# EmonDCShieldv0_1.net
KiCad netlist of a schematic drawn in EAGLE
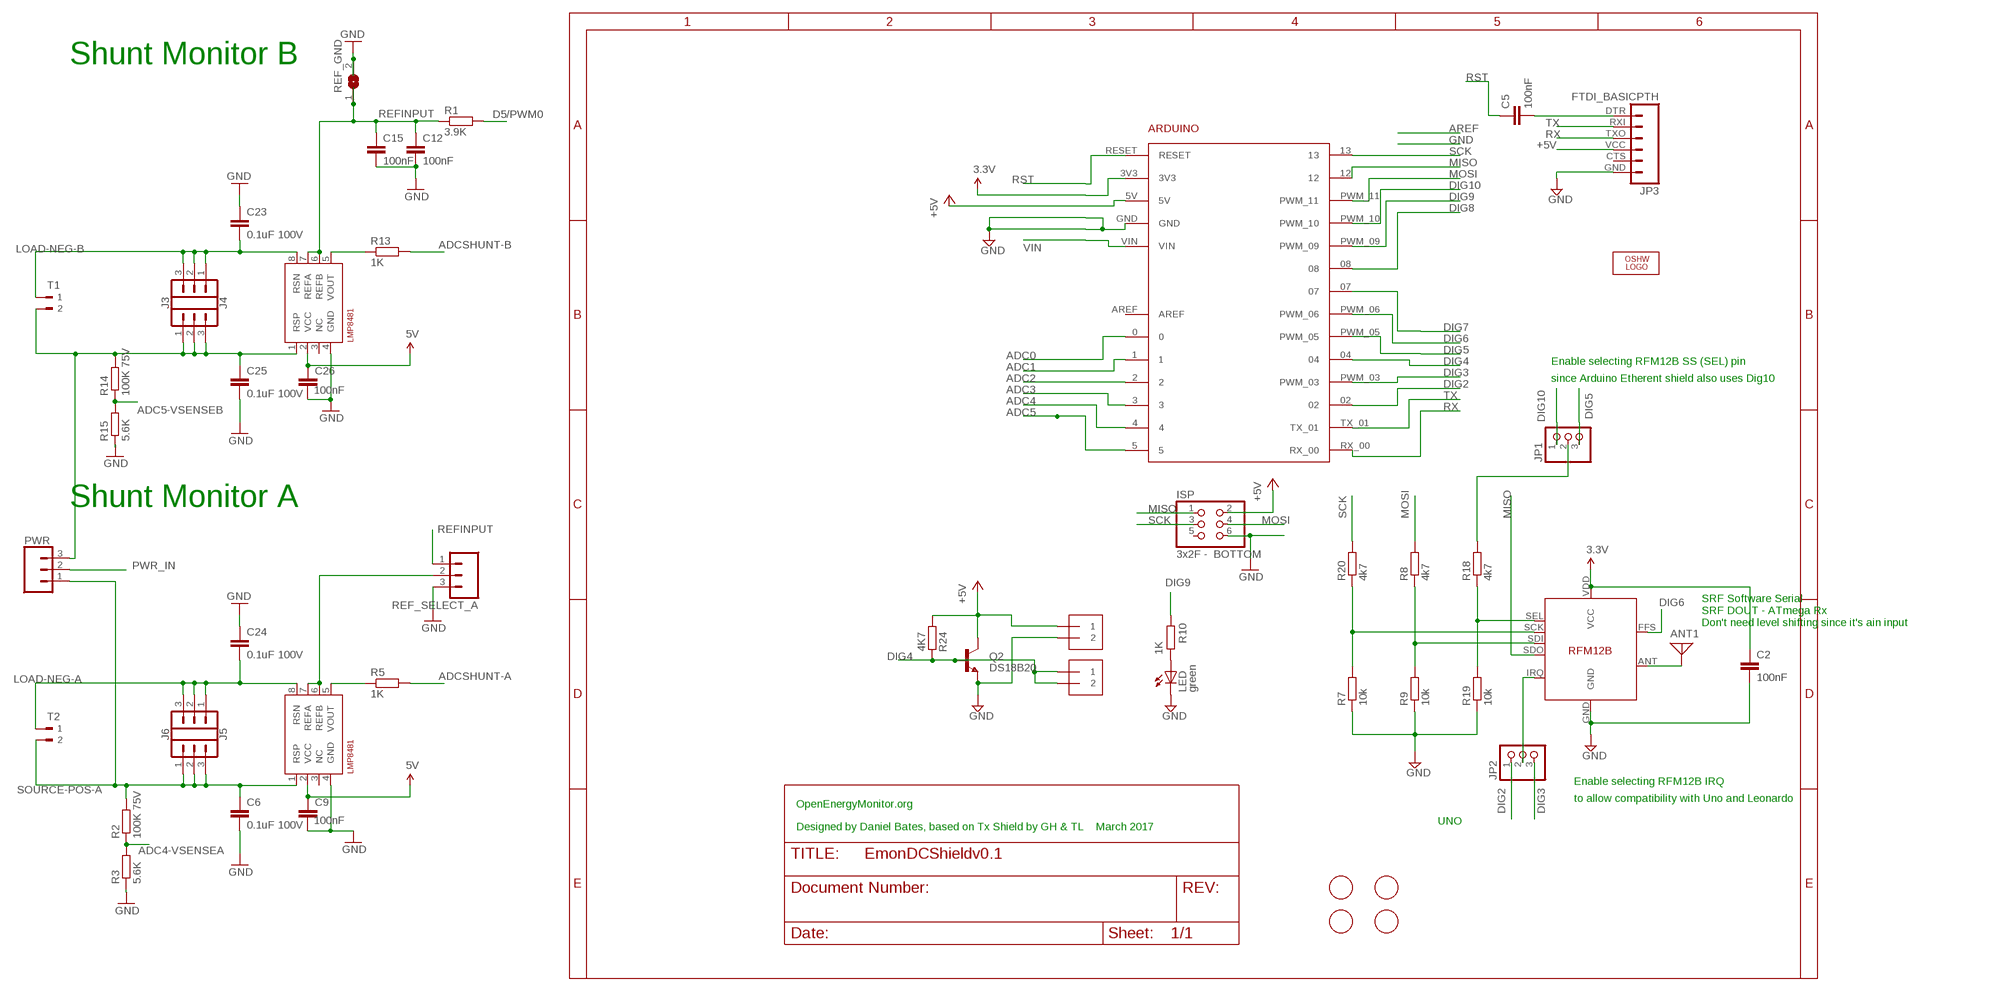
[diagram p0: schematic, sheet 1]

(export (version "E")
  (design (tool "Eeschema 10.0.6"))
  (components
    (comp (ref "ANT1")
      (value "ANTENNA")
      (footprint "eagle-import:PAD-01")
      (libsource (lib "eagle-import") (part "ANTENNA"))
    )
    (comp (ref "ARDUINO1")
      (value "ARDUINO2")
      (footprint "eagle-import:ARDUINO2")
      (libsource (lib "eagle-import") (part "ARDUINO2"))
    )
    (comp (ref "C2")
      (value "100nF")
      (footprint "eagle-import:C0603")
      (libsource (lib "eagle-import") (part "C-EUC0603"))
    )
    (comp (ref "C5")
      (value "100nF")
      (footprint "eagle-import:C0603")
      (libsource (lib "eagle-import") (part "C-EUC0603"))
    )
    (comp (ref "C6")
      (value "0.1uF 100V")
      (footprint "eagle-import:C0603")
      (fields (field (name "MPN") "C1608X7S2A104K080AB"))
      (libsource (lib "eagle-import") (part "C-EUC0603"))
    )
    (comp (ref "C9")
      (value "100nF")
      (footprint "eagle-import:C0603")
      (fields (field (name "MPN") "C1608X7S2A104K080AB"))
      (libsource (lib "eagle-import") (part "C-EUC0603"))
    )
    (comp (ref "C12")
      (value "100nF")
      (footprint "eagle-import:C0603")
      (libsource (lib "eagle-import") (part "C-EUC0603"))
    )
    (comp (ref "C15")
      (value "100nF")
      (footprint "eagle-import:C0603")
      (fields (field (name "MPN") "C1608X7S2A104K080AB"))
      (libsource (lib "eagle-import") (part "C-EUC0603"))
    )
    (comp (ref "C23")
      (value "0.1uF 100V")
      (footprint "eagle-import:C0603")
      (fields (field (name "MPN") "C1608X7S2A104K080AB"))
      (libsource (lib "eagle-import") (part "C-EUC0603"))
    )
    (comp (ref "C24")
      (value "0.1uF 100V")
      (footprint "eagle-import:C0603")
      (fields (field (name "MPN") "C1608X7S2A104K080AB"))
      (libsource (lib "eagle-import") (part "C-EUC0603"))
    )
    (comp (ref "C25")
      (value "0.1uF 100V")
      (footprint "eagle-import:C0603")
      (fields (field (name "MPN") "C1608X7S2A104K080AB"))
      (libsource (lib "eagle-import") (part "C-EUC0603"))
    )
    (comp (ref "C26")
      (value "100nF")
      (footprint "eagle-import:C0603")
      (fields (field (name "MPN") "C1608X7S2A104K080AB"))
      (libsource (lib "eagle-import") (part "C-EUC0603"))
    )
    (comp (ref "ISP")
      (value "3x2F - BOTTOM")
      (footprint "eagle-import:2X03")
      (libsource (lib "eagle-import") (part "PINHD-2X3"))
    )
    (comp (ref "J1")
      (value "1X2-3.5MM")
      (footprint "eagle-import:1X2-3.5MM")
      (libsource (lib "eagle-import") (part "1X2-3.5MM"))
    )
    (comp (ref "J2")
      (value "1X2-3.5MM")
      (footprint "eagle-import:1X2-3.5MM")
      (libsource (lib "eagle-import") (part "1X2-3.5MM"))
    )
    (comp (ref "J3")
      (value "CONN_03")
      (footprint "eagle-import:1X03")
      (libsource (lib "eagle-import") (part "CONN_03"))
    )
    (comp (ref "J4")
      (value "CONN_03")
      (footprint "eagle-import:1X03")
      (libsource (lib "eagle-import") (part "CONN_03"))
    )
    (comp (ref "J5")
      (value "CONN_03")
      (footprint "eagle-import:1X03")
      (libsource (lib "eagle-import") (part "CONN_03"))
    )
    (comp (ref "J6")
      (value "CONN_03")
      (footprint "eagle-import:1X03")
      (libsource (lib "eagle-import") (part "CONN_03"))
    )
    (comp (ref "JP1")
      (value "PINHD-1X3")
      (footprint "eagle-import:1X03")
      (libsource (lib "eagle-import") (part "PINHD-1X3"))
    )
    (comp (ref "JP2")
      (value "PINHD-1X3")
      (footprint "eagle-import:1X03")
      (libsource (lib "eagle-import") (part "PINHD-1X3"))
    )
    (comp (ref "JP3")
      (value "FTDI_BASICPTH")
      (footprint "eagle-import:FTDI_BASIC")
      (libsource (lib "eagle-import") (part "FTDI_BASICPTH"))
    )
    (comp (ref "LED")
      (value "green")
      (footprint "eagle-import:CHIPLED_0805")
      (libsource (lib "eagle-import") (part "LEDCHIPLED_0805"))
    )
    (comp (ref "LOGO1")
      (value "OSHW_LOGO_10MILX0200-NT")
      (footprint "eagle-import:OSHW_10X200_NOTEXT")
      (libsource (lib "eagle-import") (part "OSHW_LOGO_10MILX0200-NT"))
    )
    (comp (ref "PWR")
      (value "CONN_03")
      (footprint "eagle-import:1X03")
      (libsource (lib "eagle-import") (part "CONN_03"))
    )
    (comp (ref "Q2")
      (value "DS18B20")
      (footprint "eagle-import:TO-92")
      (libsource (lib "eagle-import") (part "TRANSISTOR_NPNTO92"))
    )
    (comp (ref "R1")
      (value "3.9K")
      (footprint "eagle-import:R0603")
      (libsource (lib "eagle-import") (part "R-EU_R0603"))
    )
    (comp (ref "R2")
      (value "100K 75V")
      (footprint "eagle-import:R0603")
      (fields (field (name "MPN") "MCWR06X1003FTL"))
      (libsource (lib "eagle-import") (part "R-EU_R0603"))
    )
    (comp (ref "R3")
      (value "5.6K")
      (footprint "eagle-import:R0603")
      (fields (field (name "MPN") " MCWR06X5901FTL"))
      (libsource (lib "eagle-import") (part "R-EU_R0603"))
    )
    (comp (ref "R5")
      (value "1K")
      (footprint "eagle-import:R0603")
      (libsource (lib "eagle-import") (part "R-EU_R0603"))
    )
    (comp (ref "R7")
      (value "10k")
      (footprint "eagle-import:R0603")
      (libsource (lib "eagle-import") (part "R-EU_R0603"))
    )
    (comp (ref "R8")
      (value "4k7")
      (footprint "eagle-import:R0603")
      (libsource (lib "eagle-import") (part "R-EU_R0603"))
    )
    (comp (ref "R9")
      (value "10k")
      (footprint "eagle-import:R0603")
      (libsource (lib "eagle-import") (part "R-EU_R0603"))
    )
    (comp (ref "R10")
      (value "1K")
      (footprint "eagle-import:R0603")
      (libsource (lib "eagle-import") (part "R-EU_R0603"))
    )
    (comp (ref "R13")
      (value "1K")
      (footprint "eagle-import:R0603")
      (libsource (lib "eagle-import") (part "R-EU_R0603"))
    )
    (comp (ref "R14")
      (value "100K 75V")
      (footprint "eagle-import:R0603")
      (fields (field (name "MPN") "MCWR06X1003FTL"))
      (libsource (lib "eagle-import") (part "R-EU_R0603"))
    )
    (comp (ref "R15")
      (value "5.6K")
      (footprint "eagle-import:R0603")
      (fields (field (name "MPN") " MCWR06X5901FTL"))
      (libsource (lib "eagle-import") (part "R-EU_R0603"))
    )
    (comp (ref "R18")
      (value "4k7")
      (footprint "eagle-import:R0603")
      (libsource (lib "eagle-import") (part "R-EU_R0603"))
    )
    (comp (ref "R19")
      (value "10k")
      (footprint "eagle-import:R0603")
      (libsource (lib "eagle-import") (part "R-EU_R0603"))
    )
    (comp (ref "R20")
      (value "4k7")
      (footprint "eagle-import:R0603")
      (libsource (lib "eagle-import") (part "R-EU_R0603"))
    )
    (comp (ref "R24")
      (value "4K7")
      (footprint "eagle-import:R0603")
      (libsource (lib "eagle-import") (part "R-EU_R0603"))
    )
    (comp (ref "REF_GND")
      (value "SJ")
      (footprint "eagle-import:SJ")
      (libsource (lib "eagle-import") (part "SJ"))
    )
    (comp (ref "REF_SELECT_A")
      (value "2212S-02SG-85")
      (footprint "eagle-import:1X03")
      (fields (field (name "MF") "MULTICOMP"))
      (libsource (lib "eagle-import") (part "CONN_03"))
    )
    (comp (ref "SHUNTMON-A")
      (value "LMP8481")
      (footprint "eagle-import:S-PDSO-G08")
      (fields (field (name "MF") "TEXAS INSTRUMENTS") (field (name "MPN") "LMP8481MME-S/NOPB"))
      (libsource (lib "eagle-import") (part "LMP8481LMP8481-H"))
    )
    (comp (ref "SHUNTMON-B")
      (value "LMP8481")
      (footprint "eagle-import:S-PDSO-G08")
      (fields (field (name "MF") "TEXAS INSTRUMENTS") (field (name "MPN") "LMP8481MME-H/NOPB"))
      (libsource (lib "eagle-import") (part "LMP8481LMP8481-H"))
    )
    (comp (ref "T1")
      (value "180-2")
      (footprint "eagle-import:180-2")
      (libsource (lib "eagle-import") (part "180-2"))
    )
    (comp (ref "T2")
      (value "180-2")
      (footprint "eagle-import:180-2")
      (libsource (lib "eagle-import") (part "180-2"))
    )
    (comp (ref "U$1")
      (value "FIDUCIAL")
      (footprint "eagle-import:FIDUCIAL_1MM")
      (libsource (lib "eagle-import") (part "FIDUCIAL"))
    )
    (comp (ref "U$2")
      (value "RFM12B")
      (footprint "eagle-import:RFM12B")
      (libsource (lib "eagle-import") (part "RFM12B"))
    )
    (comp (ref "U$3")
      (value "FIDUCIAL")
      (footprint "eagle-import:FIDUCIAL_1MM")
      (libsource (lib "eagle-import") (part "FIDUCIAL"))
    )
    (comp (ref "U$4")
      (value "FIDUCIAL")
      (footprint "eagle-import:FIDUCIAL_1MM")
      (libsource (lib "eagle-import") (part "FIDUCIAL"))
    )
    (comp (ref "U$5")
      (value "FIDUCIAL")
      (footprint "eagle-import:FIDUCIAL_1MM")
      (libsource (lib "eagle-import") (part "FIDUCIAL"))
    )
  )
  (nets
    (net (code "1") (name "+5V") (class "Default")
      (node (ref "ARDUINO1") (pin "5V") (pinfunction "5V_5V") (pintype "bidirectional"))
      (node (ref "ISP") (pin "2") (pinfunction "2_2") (pintype "passive"))
      (node (ref "J1") (pin "1") (pinfunction "1_1") (pintype "passive"))
      (node (ref "JP3") (pin "VCC") (pinfunction "4_VCC") (pintype "passive"))
      (node (ref "Q2") (pin "3") (pinfunction "C_3") (pintype "passive"))
      (node (ref "R24") (pin "1") (pinfunction "1_1") (pintype "passive"))
    )
    (net (code "2") (name "/ADC0") (class "Default")
      (node (ref "ARDUINO1") (pin "0") (pinfunction "0_0") (pintype "bidirectional"))
    )
    (net (code "3") (name "/ADC1") (class "Default")
      (node (ref "ARDUINO1") (pin "1") (pinfunction "1_1") (pintype "bidirectional"))
    )
    (net (code "4") (name "/ADC2") (class "Default")
      (node (ref "ARDUINO1") (pin "2") (pinfunction "2_2") (pintype "bidirectional"))
    )
    (net (code "5") (name "/ADC3") (class "Default")
      (node (ref "ARDUINO1") (pin "3") (pinfunction "3_3") (pintype "bidirectional"))
    )
    (net (code "6") (name "/ADC4") (class "Default")
      (node (ref "ARDUINO1") (pin "4") (pinfunction "4_4") (pintype "bidirectional"))
    )
    (net (code "7") (name "/ADC4-VSENSEA") (class "Default")
      (node (ref "R2") (pin "1") (pinfunction "1_1") (pintype "passive"))
      (node (ref "R3") (pin "2") (pinfunction "2_2") (pintype "passive"))
    )
    (net (code "8") (name "/ADC5") (class "Default")
      (node (ref "ARDUINO1") (pin "5") (pinfunction "5_5") (pintype "bidirectional"))
    )
    (net (code "9") (name "/ADC5-VSENSEB") (class "Default")
      (node (ref "R14") (pin "1") (pinfunction "1_1") (pintype "passive"))
      (node (ref "R15") (pin "2") (pinfunction "2_2") (pintype "passive"))
    )
    (net (code "10") (name "/ADCSHUNT-A") (class "Default")
      (node (ref "R5") (pin "2") (pinfunction "2_2") (pintype "passive"))
    )
    (net (code "11") (name "/ADCSHUNT-B") (class "Default")
      (node (ref "R13") (pin "2") (pinfunction "2_2") (pintype "passive"))
    )
    (net (code "13") (name "/D5{slash}PWM0") (class "Default")
      (node (ref "R1") (pin "2") (pinfunction "2_2") (pintype "passive"))
    )
    (net (code "14") (name "/DIG2") (class "Default")
      (node (ref "ARDUINO1") (pin "02") (pinfunction "02_02") (pintype "bidirectional"))
      (node (ref "JP2") (pin "1") (pinfunction "1_1") (pintype "passive"))
    )
    (net (code "15") (name "/DIG3") (class "Default")
      (node (ref "ARDUINO1") (pin "PWM_03") (pinfunction "PWM_03_PWM_03") (pintype "bidirectional"))
      (node (ref "JP2") (pin "3") (pinfunction "3_3") (pintype "passive"))
    )
    (net (code "16") (name "/DIG4") (class "Default")
      (node (ref "ARDUINO1") (pin "04") (pinfunction "04_04") (pintype "bidirectional"))
      (node (ref "J2") (pin "1") (pinfunction "1_1") (pintype "passive"))
      (node (ref "J2") (pin "2") (pinfunction "2_2") (pintype "passive"))
      (node (ref "Q2") (pin "2") (pinfunction "B_2") (pintype "passive"))
      (node (ref "R24") (pin "2") (pinfunction "2_2") (pintype "passive"))
    )
    (net (code "17") (name "/DIG5") (class "Default")
      (node (ref "ARDUINO1") (pin "PWM_05") (pinfunction "PWM_05_PWM_05") (pintype "bidirectional"))
      (node (ref "JP1") (pin "3") (pinfunction "3_3") (pintype "passive"))
    )
    (net (code "18") (name "/DIG6") (class "Default")
      (node (ref "ARDUINO1") (pin "PWM_06") (pinfunction "PWM_06_PWM_06") (pintype "bidirectional"))
      (node (ref "U$2") (pin "FFS") (pinfunction "FFS_FFS") (pintype "bidirectional"))
    )
    (net (code "19") (name "/DIG7") (class "Default")
      (node (ref "ARDUINO1") (pin "07") (pinfunction "07_07") (pintype "bidirectional"))
    )
    (net (code "20") (name "/DIG8") (class "Default")
      (node (ref "ARDUINO1") (pin "08") (pinfunction "08_08") (pintype "bidirectional"))
    )
    (net (code "21") (name "/DIG9") (class "Default")
      (node (ref "ARDUINO1") (pin "PWM_09") (pinfunction "PWM_09_PWM_09") (pintype "bidirectional"))
      (node (ref "R10") (pin "2") (pinfunction "2_2") (pintype "passive"))
    )
    (net (code "22") (name "/DIG10") (class "Default")
      (node (ref "ARDUINO1") (pin "PWM_10") (pinfunction "PWM_10_PWM_10") (pintype "bidirectional"))
      (node (ref "JP1") (pin "1") (pinfunction "1_1") (pintype "passive"))
    )
    (net (code "23") (name "/LOAD-NEG-A") (class "Default")
      (node (ref "C24") (pin "2") (pinfunction "2_2") (pintype "passive"))
      (node (ref "J6") (pin "1") (pinfunction "1_1") (pintype "passive"))
      (node (ref "J6") (pin "2") (pinfunction "2_2") (pintype "passive"))
      (node (ref "J6") (pin "3") (pinfunction "3_3") (pintype "passive"))
      (node (ref "SHUNTMON-B") (pin "8") (pinfunction "RSN_8") (pintype "bidirectional"))
      (node (ref "T2") (pin "1") (pinfunction "1_1") (pintype "passive"))
    )
    (net (code "24") (name "/LOAD-NEG-B") (class "Default")
      (node (ref "C23") (pin "2") (pinfunction "2_2") (pintype "passive"))
      (node (ref "J3") (pin "1") (pinfunction "1_1") (pintype "passive"))
      (node (ref "J3") (pin "2") (pinfunction "2_2") (pintype "passive"))
      (node (ref "J3") (pin "3") (pinfunction "3_3") (pintype "passive"))
      (node (ref "SHUNTMON-A") (pin "8") (pinfunction "RSN_8") (pintype "bidirectional"))
      (node (ref "T1") (pin "1") (pinfunction "1_1") (pintype "passive"))
    )
    (net (code "25") (name "/MISO") (class "Default")
      (node (ref "ARDUINO1") (pin "12") (pinfunction "12_12") (pintype "bidirectional"))
      (node (ref "ISP") (pin "1") (pinfunction "1_1") (pintype "passive"))
      (node (ref "U$2") (pin "SDO") (pinfunction "SDO_SDO") (pintype "output"))
    )
    (net (code "26") (name "/MOSI") (class "Default")
      (node (ref "ARDUINO1") (pin "PWM_11") (pinfunction "PWM_11_PWM_11") (pintype "bidirectional"))
      (node (ref "ISP") (pin "4") (pinfunction "4_4") (pintype "passive"))
      (node (ref "R8") (pin "2") (pinfunction "2_2") (pintype "passive"))
    )
    (net (code "27") (name "/PWR_IN") (class "Default")
      (node (ref "PWR") (pin "2") (pinfunction "2_2") (pintype "passive"))
    )
    (net (code "28") (name "/REFINPUT") (class "Default")
      (node (ref "C12") (pin "1") (pinfunction "1_1") (pintype "passive"))
      (node (ref "C15") (pin "1") (pinfunction "1_1") (pintype "passive"))
      (node (ref "R1") (pin "1") (pinfunction "1_1") (pintype "passive"))
      (node (ref "REF_GND") (pin "1") (pinfunction "1_1") (pintype "passive"))
      (node (ref "REF_SELECT_A") (pin "1") (pinfunction "1_1") (pintype "passive"))
      (node (ref "SHUNTMON-A") (pin "6") (pinfunction "REFB_6") (pintype "bidirectional"))
      (node (ref "SHUNTMON-A") (pin "7") (pinfunction "REFA_7") (pintype "bidirectional"))
    )
    (net (code "29") (name "/RST") (class "Default")
      (node (ref "ARDUINO1") (pin "RESET") (pinfunction "RESET_RESET") (pintype "bidirectional"))
      (node (ref "C5") (pin "1") (pinfunction "1_1") (pintype "passive"))
    )
    (net (code "30") (name "/RX") (class "Default")
      (node (ref "ARDUINO1") (pin "RX_00") (pinfunction "RX_00_RX_00") (pintype "bidirectional"))
      (node (ref "JP3") (pin "TXO") (pinfunction "3_TXO") (pintype "passive"))
    )
    (net (code "31") (name "/SCK") (class "Default")
      (node (ref "ARDUINO1") (pin "13") (pinfunction "13_13") (pintype "bidirectional"))
      (node (ref "ISP") (pin "3") (pinfunction "3_3") (pintype "passive"))
      (node (ref "R20") (pin "2") (pinfunction "2_2") (pintype "passive"))
    )
    (net (code "32") (name "/SOURCE-POS-A") (class "Default")
      (node (ref "C6") (pin "1") (pinfunction "1_1") (pintype "passive"))
      (node (ref "J5") (pin "1") (pinfunction "1_1") (pintype "passive"))
      (node (ref "J5") (pin "2") (pinfunction "2_2") (pintype "passive"))
      (node (ref "J5") (pin "3") (pinfunction "3_3") (pintype "passive"))
      (node (ref "PWR") (pin "1") (pinfunction "1_1") (pintype "passive"))
      (node (ref "R2") (pin "2") (pinfunction "2_2") (pintype "passive"))
      (node (ref "SHUNTMON-B") (pin "1") (pinfunction "RSP_1") (pintype "bidirectional"))
      (node (ref "T2") (pin "2") (pinfunction "2_2") (pintype "passive"))
    )
    (net (code "33") (name "/TX") (class "Default")
      (node (ref "ARDUINO1") (pin "TX_01") (pinfunction "TX_01_TX_01") (pintype "bidirectional"))
      (node (ref "JP3") (pin "RXI") (pinfunction "2_RXI") (pintype "passive"))
    )
    (net (code "34") (name "/VIN") (class "Default")
      (node (ref "ARDUINO1") (pin "VIN") (pinfunction "VIN_VIN") (pintype "bidirectional"))
    )
    (net (code "35") (name "3.3V") (class "Default")
      (node (ref "ARDUINO1") (pin "3V3") (pinfunction "3V3_3V3") (pintype "bidirectional"))
      (node (ref "C2") (pin "1") (pinfunction "1_1") (pintype "passive"))
      (node (ref "U$2") (pin "VDD") (pinfunction "VCC_VDD") (pintype "power_in"))
    )
    (net (code "36") (name "5V") (class "Default")
      (node (ref "C26") (pin "1") (pinfunction "1_1") (pintype "passive"))
      (node (ref "C9") (pin "1") (pinfunction "1_1") (pintype "passive"))
      (node (ref "SHUNTMON-A") (pin "2") (pinfunction "VCC_2") (pintype "bidirectional"))
      (node (ref "SHUNTMON-B") (pin "2") (pinfunction "VCC_2") (pintype "bidirectional"))
    )
    (net (code "37") (name "GND") (class "Default")
      (node (ref "ARDUINO1") (pin "GND") (pinfunction "GND_GND") (pintype "bidirectional"))
      (node (ref "C12") (pin "2") (pinfunction "2_2") (pintype "passive"))
      (node (ref "C15") (pin "2") (pinfunction "2_2") (pintype "passive"))
      (node (ref "C2") (pin "2") (pinfunction "2_2") (pintype "passive"))
      (node (ref "C23") (pin "1") (pinfunction "1_1") (pintype "passive"))
      (node (ref "C24") (pin "1") (pinfunction "1_1") (pintype "passive"))
      (node (ref "C25") (pin "2") (pinfunction "2_2") (pintype "passive"))
      (node (ref "C26") (pin "2") (pinfunction "2_2") (pintype "passive"))
      (node (ref "C6") (pin "2") (pinfunction "2_2") (pintype "passive"))
      (node (ref "C9") (pin "2") (pinfunction "2_2") (pintype "passive"))
      (node (ref "ISP") (pin "6") (pinfunction "6_6") (pintype "passive"))
      (node (ref "J1") (pin "2") (pinfunction "2_2") (pintype "passive"))
      (node (ref "JP3") (pin "GND") (pinfunction "6_GND") (pintype "passive"))
      (node (ref "LED") (pin "C") (pinfunction "C_C") (pintype "passive"))
      (node (ref "Q2") (pin "1") (pinfunction "E_1") (pintype "passive"))
      (node (ref "R15") (pin "1") (pinfunction "1_1") (pintype "passive"))
      (node (ref "R19") (pin "1") (pinfunction "1_1") (pintype "passive"))
      (node (ref "R3") (pin "1") (pinfunction "1_1") (pintype "passive"))
      (node (ref "R7") (pin "1") (pinfunction "1_1") (pintype "passive"))
      (node (ref "R9") (pin "1") (pinfunction "1_1") (pintype "passive"))
      (node (ref "REF_GND") (pin "2") (pinfunction "2_2") (pintype "passive"))
      (node (ref "REF_SELECT_A") (pin "3") (pinfunction "3_3") (pintype "passive"))
      (node (ref "SHUNTMON-A") (pin "4") (pinfunction "GND_4") (pintype "bidirectional"))
      (node (ref "SHUNTMON-B") (pin "4") (pinfunction "GND_4") (pintype "bidirectional"))
      (node (ref "U$2") (pin "GND") (pinfunction "GND_GND") (pintype "power_in"))
    )
    (net (code "38") (name "Net-(ANT1-Pad1)") (class "Default")
      (node (ref "ANT1") (pin "1") (pinfunction "1_1") (pintype "output"))
      (node (ref "U$2") (pin "ANT") (pinfunction "ANT_ANT") (pintype "passive"))
    )
    (net (code "39") (name "Net-(JP1-Pad2)") (class "Default")
      (node (ref "JP1") (pin "2") (pinfunction "2_2") (pintype "passive"))
      (node (ref "R18") (pin "2") (pinfunction "2_2") (pintype "passive"))
    )
    (net (code "40") (name "Net-(JP2-Pad2)") (class "Default")
      (node (ref "JP2") (pin "2") (pinfunction "2_2") (pintype "passive"))
      (node (ref "U$2") (pin "IRQ") (pinfunction "IRQ_IRQ") (pintype "open_collector"))
    )
    (net (code "41") (name "Net-(JP3-1)") (class "Default")
      (node (ref "C5") (pin "2") (pinfunction "2_2") (pintype "passive"))
      (node (ref "JP3") (pin "DTR") (pinfunction "1_DTR") (pintype "passive"))
    )
    (net (code "42") (name "Net-(LED-PadA)") (class "Default")
      (node (ref "LED") (pin "A") (pinfunction "A_A") (pintype "passive"))
      (node (ref "R10") (pin "1") (pinfunction "1_1") (pintype "passive"))
    )
    (net (code "43") (name "Net-(R8-Pad1)") (class "Default")
      (node (ref "R8") (pin "1") (pinfunction "1_1") (pintype "passive"))
      (node (ref "R9") (pin "2") (pinfunction "2_2") (pintype "passive"))
      (node (ref "U$2") (pin "SDI") (pinfunction "SDI_SDI") (pintype "input"))
    )
    (net (code "44") (name "Net-(R18-Pad1)") (class "Default")
      (node (ref "R18") (pin "1") (pinfunction "1_1") (pintype "passive"))
      (node (ref "R19") (pin "2") (pinfunction "2_2") (pintype "passive"))
      (node (ref "U$2") (pin "SEL") (pinfunction "SEL_SEL") (pintype "input"))
    )
    (net (code "45") (name "Net-(R20-Pad1)") (class "Default")
      (node (ref "R20") (pin "1") (pinfunction "1_1") (pintype "passive"))
      (node (ref "R7") (pin "2") (pinfunction "2_2") (pintype "passive"))
      (node (ref "U$2") (pin "SCK") (pinfunction "SCK_SCK") (pintype "input"))
    )
    (net (code "46") (name "Net-(SHUNTMON-A-RSP)") (class "Default")
      (node (ref "C25") (pin "1") (pinfunction "1_1") (pintype "passive"))
      (node (ref "J4") (pin "1") (pinfunction "1_1") (pintype "passive"))
      (node (ref "J4") (pin "2") (pinfunction "2_2") (pintype "passive"))
      (node (ref "J4") (pin "3") (pinfunction "3_3") (pintype "passive"))
      (node (ref "PWR") (pin "3") (pinfunction "3_3") (pintype "passive"))
      (node (ref "R14") (pin "2") (pinfunction "2_2") (pintype "passive"))
      (node (ref "SHUNTMON-A") (pin "1") (pinfunction "RSP_1") (pintype "bidirectional"))
      (node (ref "T1") (pin "2") (pinfunction "2_2") (pintype "passive"))
    )
    (net (code "47") (name "Net-(SHUNTMON-A-VOUT)") (class "Default")
      (node (ref "R13") (pin "1") (pinfunction "1_1") (pintype "passive"))
      (node (ref "SHUNTMON-A") (pin "5") (pinfunction "VOUT_5") (pintype "bidirectional"))
    )
    (net (code "48") (name "Net-(SHUNTMON-B-REFA)") (class "Default")
      (node (ref "REF_SELECT_A") (pin "2") (pinfunction "2_2") (pintype "passive"))
      (node (ref "SHUNTMON-B") (pin "6") (pinfunction "REFB_6") (pintype "bidirectional"))
      (node (ref "SHUNTMON-B") (pin "7") (pinfunction "REFA_7") (pintype "bidirectional"))
    )
    (net (code "49") (name "Net-(SHUNTMON-B-VOUT)") (class "Default")
      (node (ref "R5") (pin "1") (pinfunction "1_1") (pintype "passive"))
      (node (ref "SHUNTMON-B") (pin "5") (pinfunction "VOUT_5") (pintype "bidirectional"))
    )
    (net (code "50") (name "unconnected-(ARDUINO1-PadAREF)") (class "Default")
      (node (ref "ARDUINO1") (pin "AREF") (pinfunction "AREF_AREF") (pintype "bidirectional"))
    )
    (net (code "51") (name "unconnected-(ISP-Pad5)") (class "Default")
      (node (ref "ISP") (pin "5") (pinfunction "5_5") (pintype "passive"))
    )
    (net (code "52") (name "unconnected-(JP3-5-PadCTS)") (class "Default")
      (node (ref "JP3") (pin "CTS") (pinfunction "5_CTS") (pintype "passive"))
    )
    (net (code "53") (name "unconnected-(SHUNTMON-A-NC-Pad3)") (class "Default")
      (node (ref "SHUNTMON-A") (pin "3") (pinfunction "NC_3") (pintype "bidirectional"))
    )
    (net (code "54") (name "unconnected-(SHUNTMON-B-NC-Pad3)") (class "Default")
      (node (ref "SHUNTMON-B") (pin "3") (pinfunction "NC_3") (pintype "bidirectional"))
    )
  )
)
